# 220VAC_to_24Vdc.net
KiCad netlist of a schematic drawn in Altium Designer
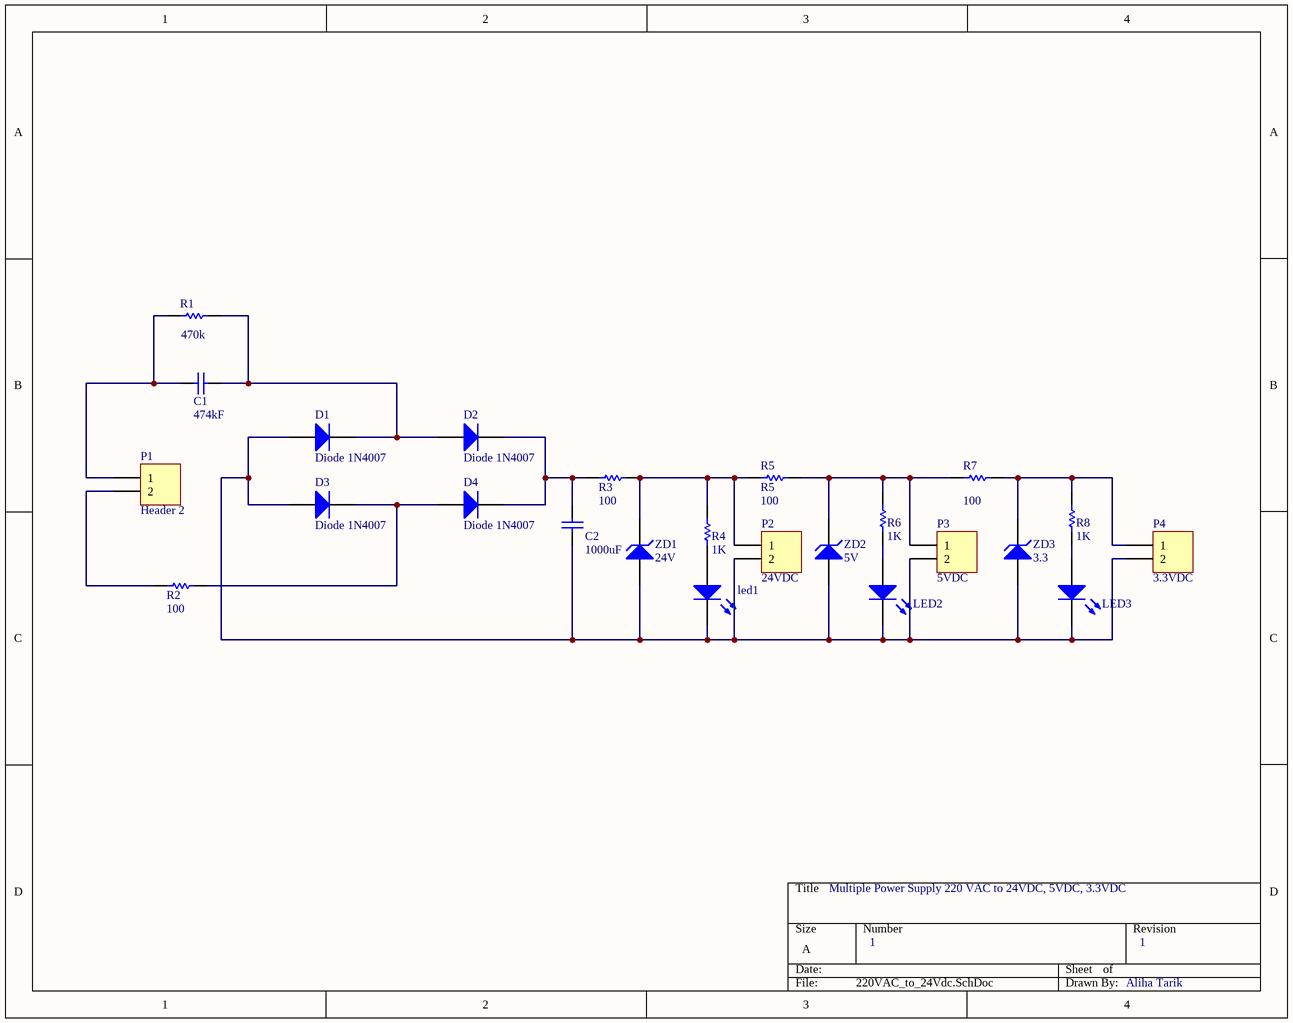
[diagram p0: 220VAC_to_24Vdc.SchDoc]

(export (version "E")
  (design (tool "Eeschema 10.0.6"))
  (components
    (comp (ref "C1")
      (value "C1")
      (footprint "RAD-0.3")
      (description "Capacitor")
      (fields (field (name "C1") "474kF") (field (name "PUBLISHER") "Altium Limited"))
      (libsource (lib "Miscellaneous Devices") (part "Cap"))
    )
    (comp (ref "C2")
      (value "C2")
      (footprint "RAD-0.3")
      (description "Capacitor")
      (fields (field (name "ALTIUM_VALUE") "1000uF") (field (name "PUBLISHER") "Altium Limited"))
      (libsource (lib "Miscellaneous Devices") (part "Cap"))
    )
    (comp (ref "D1")
      (value "Diode 1N4007")
      (footprint "DO-41")
      (description "1 Amp General Purpose Rectifier")
      (fields (field (name "PUBLISHER") "Altium Limited"))
      (libsource (lib "Miscellaneous Devices") (part "Diode 1N4007"))
    )
    (comp (ref "D2")
      (value "Diode 1N4007")
      (footprint "DO-41")
      (description "1 Amp General Purpose Rectifier")
      (fields (field (name "PUBLISHER") "Altium Limited"))
      (libsource (lib "Miscellaneous Devices") (part "Diode 1N4007"))
    )
    (comp (ref "D3")
      (value "Diode 1N4007")
      (footprint "DO-41")
      (description "1 Amp General Purpose Rectifier")
      (fields (field (name "PUBLISHER") "Altium Limited"))
      (libsource (lib "Miscellaneous Devices") (part "Diode 1N4007"))
    )
    (comp (ref "D4")
      (value "Diode 1N4007")
      (footprint "DO-41")
      (description "1 Amp General Purpose Rectifier")
      (fields (field (name "PUBLISHER") "Altium Limited"))
      (libsource (lib "Miscellaneous Devices") (part "Diode 1N4007"))
    )
    (comp (ref "led1")
      (value "LED1")
      (footprint "3.2X1.6X1.1")
      (description "Typical RED, GREEN, YELLOW, AMBER GaAs LED")
      (fields (field (name "PUBLISHER") "Altium Limited"))
      (libsource (lib "Miscellaneous Devices") (part "LED2"))
    )
    (comp (ref "led2")
      (value "LED2")
      (footprint "3.2X1.6X1.1")
      (description "Typical RED, GREEN, YELLOW, AMBER GaAs LED")
      (fields (field (name "PUBLISHER") "Altium Limited"))
      (libsource (lib "Miscellaneous Devices") (part "LED2"))
    )
    (comp (ref "led3")
      (value "LED3")
      (footprint "3.2X1.6X1.1")
      (description "Typical RED, GREEN, YELLOW, AMBER GaAs LED")
      (fields (field (name "PUBLISHER") "Altium Limited"))
      (libsource (lib "Miscellaneous Devices") (part "LED2"))
    )
    (comp (ref "P1")
      (value "Header 2")
      (footprint "HDR1X2")
      (description "Header, 2-Pin")
      (fields (field (name "PUBLISHER") "Altium Limited"))
      (libsource (lib "Miscellaneous Connectors") (part "Header 2"))
    )
    (comp (ref "P2")
      (value "24VDC")
      (footprint "HDR1X2")
      (description "Header, 2-Pin")
      (fields (field (name "PUBLISHER") "Altium Limited"))
      (libsource (lib "Miscellaneous Connectors") (part "Header 2"))
    )
    (comp (ref "P3")
      (value "5VDC")
      (footprint "HDR1X2")
      (description "Header, 2-Pin")
      (fields (field (name "PUBLISHER") "Altium Limited"))
      (libsource (lib "Miscellaneous Connectors") (part "Header 2"))
    )
    (comp (ref "P4")
      (value "3.3VDC")
      (footprint "HDR1X2")
      (description "Header, 2-Pin")
      (fields (field (name "PUBLISHER") "Altium Limited"))
      (libsource (lib "Miscellaneous Connectors") (part "Header 2"))
    )
    (comp (ref "R1")
      (value "470k")
      (footprint "AXIAL-0.5")
      (description "Semiconductor Resistor")
      (fields (field (name "Comment") "Res Semi") (field (name "PUBLISHER") "Altium Limited"))
      (libsource (lib "Miscellaneous Devices") (part "Res Semi"))
    )
    (comp (ref "R2")
      (value "R2")
      (footprint "AXIAL-0.5")
      (description "Semiconductor Resistor")
      (fields (field (name "ALTIUM_VALUE") "100") (field (name "PUBLISHER") "Altium Limited"))
      (libsource (lib "Miscellaneous Devices") (part "Res Semi"))
    )
    (comp (ref "R3")
      (value "R3")
      (footprint "AXIAL-0.5")
      (description "Semiconductor Resistor")
      (fields (field (name "ALTIUM_VALUE") "100") (field (name "PUBLISHER") "Altium Limited"))
      (libsource (lib "Miscellaneous Devices") (part "Res Semi"))
    )
    (comp (ref "R4")
      (value "R4")
      (footprint "AXIAL-0.5")
      (description "Semiconductor Resistor")
      (fields (field (name "ALTIUM_VALUE") "1K") (field (name "PUBLISHER") "Altium Limited"))
      (libsource (lib "Miscellaneous Devices") (part "Res Semi"))
    )
    (comp (ref "R5")
      (value "R5")
      (footprint "AXIAL-0.5")
      (description "Semiconductor Resistor")
      (fields (field (name "ALTIUM_VALUE") "100") (field (name "PUBLISHER") "Altium Limited"))
      (libsource (lib "Miscellaneous Devices") (part "Res Semi"))
    )
    (comp (ref "R6")
      (value "R6")
      (footprint "AXIAL-0.5")
      (description "Semiconductor Resistor")
      (fields (field (name "ALTIUM_VALUE") "1K") (field (name "PUBLISHER") "Altium Limited"))
      (libsource (lib "Miscellaneous Devices") (part "Res Semi"))
    )
    (comp (ref "R7")
      (value "100")
      (footprint "AXIAL-0.5")
      (description "Semiconductor Resistor")
      (fields (field (name "Comment") "R3") (field (name "PUBLISHER") "Altium Limited"))
      (libsource (lib "Miscellaneous Devices") (part "Res Semi"))
    )
    (comp (ref "R8")
      (value "R8")
      (footprint "AXIAL-0.5")
      (description "Semiconductor Resistor")
      (fields (field (name "ALTIUM_VALUE") "1K") (field (name "PUBLISHER") "Altium Limited"))
      (libsource (lib "Miscellaneous Devices") (part "Res Semi"))
    )
    (comp (ref "ZD1")
      (value "24V")
      (footprint "DIODE-0.7")
      (description "Zener Diode")
      (fields (field (name "PUBLISHER") "Altium Limited"))
      (libsource (lib "Miscellaneous Devices") (part "D Zener"))
    )
    (comp (ref "ZD2")
      (value "5V")
      (footprint "DIODE-0.7")
      (description "Zener Diode")
      (fields (field (name "PUBLISHER") "Altium Limited"))
      (libsource (lib "Miscellaneous Devices") (part "D Zener"))
    )
    (comp (ref "ZD3")
      (value "3.3")
      (footprint "DIODE-0.7")
      (description "Zener Diode")
      (fields (field (name "PUBLISHER") "Altium Limited"))
      (libsource (lib "Miscellaneous Devices") (part "D Zener"))
    )
  )
  (nets
    (net (code "1") (name "Net-(C1-Pad1)") (class "Default")
      (node (ref "C1") (pin "1") (pinfunction "1_1") (pintype "passive"))
      (node (ref "P1") (pin "1") (pinfunction "1_1") (pintype "passive"))
      (node (ref "R1") (pin "1") (pinfunction "1_1") (pintype "passive"))
    )
    (net (code "2") (name "Net-(D1-A)") (class "Default")
      (node (ref "C2") (pin "1") (pinfunction "1_1") (pintype "passive"))
      (node (ref "D1") (pin "1") (pinfunction "A_1") (pintype "passive"))
      (node (ref "D3") (pin "1") (pinfunction "A_1") (pintype "passive"))
      (node (ref "P2") (pin "2") (pinfunction "2_2") (pintype "passive"))
      (node (ref "P3") (pin "2") (pinfunction "2_2") (pintype "passive"))
      (node (ref "P4") (pin "2") (pinfunction "2_2") (pintype "passive"))
      (node (ref "ZD1") (pin "1") (pinfunction "A_1") (pintype "passive"))
      (node (ref "ZD2") (pin "1") (pinfunction "A_1") (pintype "passive"))
      (node (ref "ZD3") (pin "1") (pinfunction "A_1") (pintype "passive"))
      (node (ref "led1") (pin "2") (pinfunction "K_2") (pintype "passive"))
      (node (ref "led2") (pin "2") (pinfunction "K_2") (pintype "passive"))
      (node (ref "led3") (pin "2") (pinfunction "K_2") (pintype "passive"))
    )
    (net (code "3") (name "Net-(D1-K)") (class "Default")
      (node (ref "C1") (pin "2") (pinfunction "2_2") (pintype "passive"))
      (node (ref "D1") (pin "2") (pinfunction "K_2") (pintype "passive"))
      (node (ref "D2") (pin "1") (pinfunction "A_1") (pintype "passive"))
      (node (ref "R1") (pin "2") (pinfunction "2_2") (pintype "passive"))
    )
    (net (code "4") (name "Net-(D2-K)") (class "Default")
      (node (ref "C2") (pin "2") (pinfunction "2_2") (pintype "passive"))
      (node (ref "D2") (pin "2") (pinfunction "K_2") (pintype "passive"))
      (node (ref "D4") (pin "2") (pinfunction "K_2") (pintype "passive"))
      (node (ref "R3") (pin "1") (pinfunction "1_1") (pintype "passive"))
    )
    (net (code "5") (name "Net-(D3-K)") (class "Default")
      (node (ref "D3") (pin "2") (pinfunction "K_2") (pintype "passive"))
      (node (ref "D4") (pin "1") (pinfunction "A_1") (pintype "passive"))
      (node (ref "R2") (pin "2") (pinfunction "2_2") (pintype "passive"))
    )
    (net (code "6") (name "Net-(P1-Pad2)") (class "Default")
      (node (ref "P1") (pin "2") (pinfunction "2_2") (pintype "passive"))
      (node (ref "R2") (pin "1") (pinfunction "1_1") (pintype "passive"))
    )
    (net (code "7") (name "Net-(ZD1-K)") (class "Default")
      (node (ref "P2") (pin "1") (pinfunction "1_1") (pintype "passive"))
      (node (ref "R3") (pin "2") (pinfunction "2_2") (pintype "passive"))
      (node (ref "R4") (pin "2") (pinfunction "2_2") (pintype "passive"))
      (node (ref "R5") (pin "1") (pinfunction "1_1") (pintype "passive"))
      (node (ref "ZD1") (pin "2") (pinfunction "K_2") (pintype "passive"))
    )
    (net (code "8") (name "Net-(ZD2-K)") (class "Default")
      (node (ref "P3") (pin "1") (pinfunction "1_1") (pintype "passive"))
      (node (ref "R5") (pin "2") (pinfunction "2_2") (pintype "passive"))
      (node (ref "R6") (pin "2") (pinfunction "2_2") (pintype "passive"))
      (node (ref "R7") (pin "1") (pinfunction "1_1") (pintype "passive"))
      (node (ref "ZD2") (pin "2") (pinfunction "K_2") (pintype "passive"))
    )
    (net (code "9") (name "Net-(ZD3-K)") (class "Default")
      (node (ref "P4") (pin "1") (pinfunction "1_1") (pintype "passive"))
      (node (ref "R7") (pin "2") (pinfunction "2_2") (pintype "passive"))
      (node (ref "R8") (pin "2") (pinfunction "2_2") (pintype "passive"))
      (node (ref "ZD3") (pin "2") (pinfunction "K_2") (pintype "passive"))
    )
    (net (code "10") (name "Net-(led1-A)") (class "Default")
      (node (ref "R4") (pin "1") (pinfunction "1_1") (pintype "passive"))
      (node (ref "led1") (pin "1") (pinfunction "A_1") (pintype "passive"))
    )
    (net (code "11") (name "Net-(led2-A)") (class "Default")
      (node (ref "R6") (pin "1") (pinfunction "1_1") (pintype "passive"))
      (node (ref "led2") (pin "1") (pinfunction "A_1") (pintype "passive"))
    )
    (net (code "12") (name "Net-(led3-A)") (class "Default")
      (node (ref "R8") (pin "1") (pinfunction "1_1") (pintype "passive"))
      (node (ref "led3") (pin "1") (pinfunction "A_1") (pintype "passive"))
    )
  )
)
